# 12V_15V.net
KiCad netlist of a schematic drawn in Altium Designer
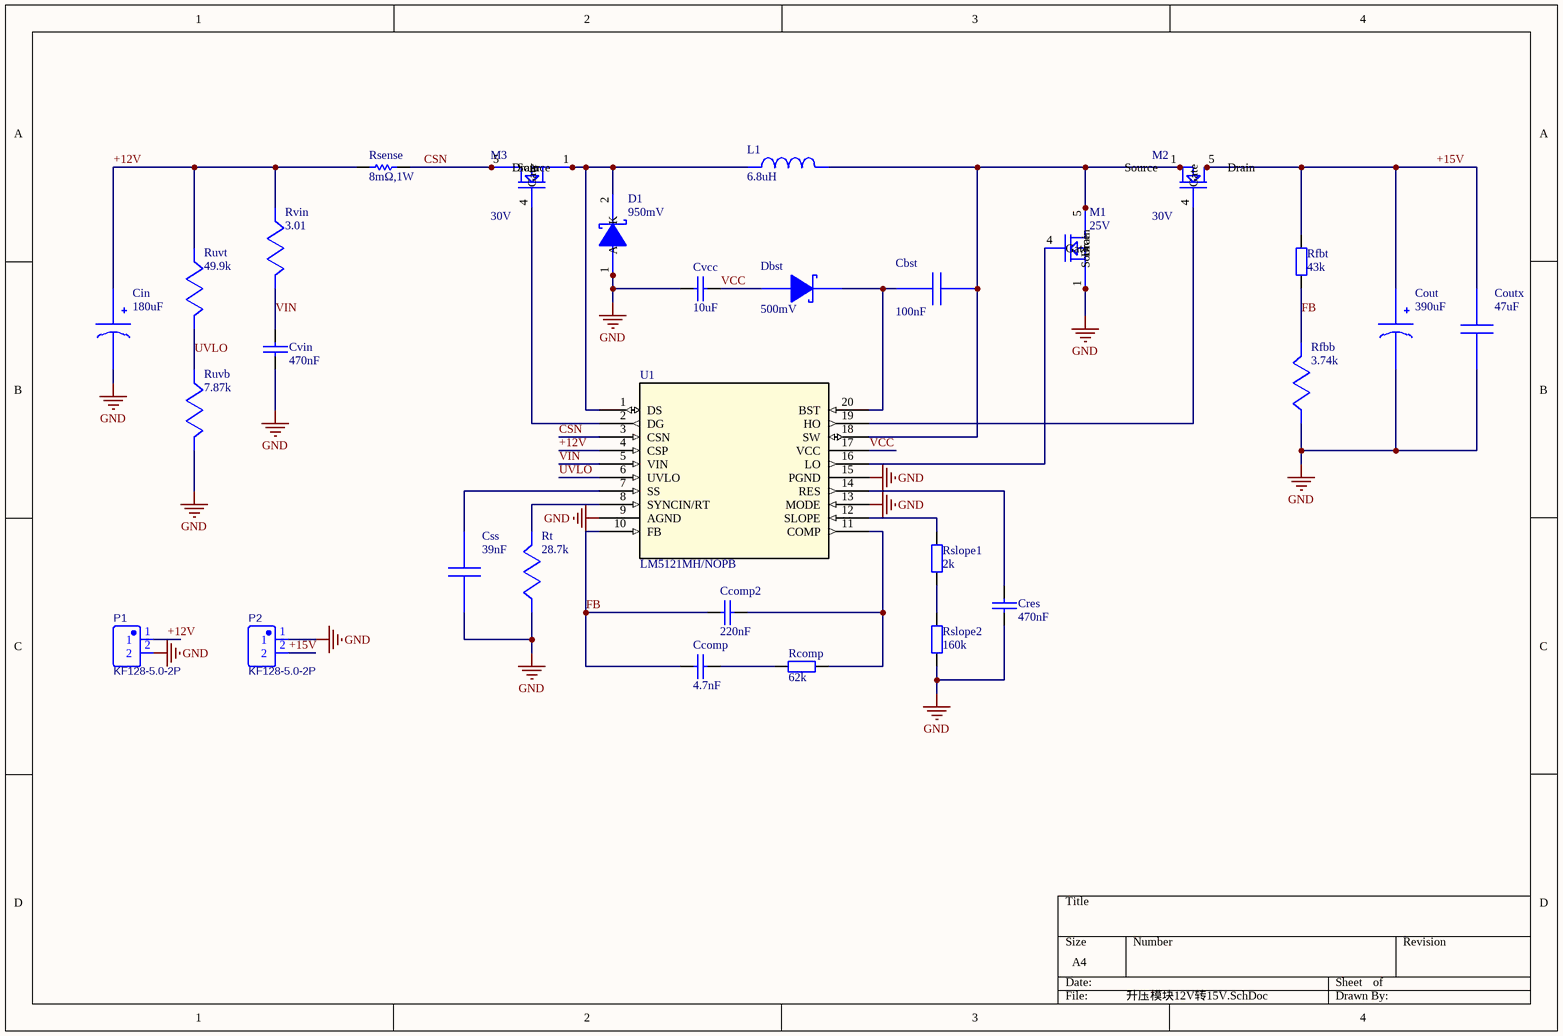
[diagram p0: 升压模块12V转15V.SchDoc]

(export (version "E")
  (design (tool "Eeschema 10.0.6"))
  (components
    (comp (ref "Cbst")
      (value "100nF")
      (footprint "0805")
      (description "C0805C104M5RACTU")
      (libsource (lib "TI") (part "Cbst"))
    )
    (comp (ref "Ccomp")
      (value "4.7nF")
      (footprint "0805C")
      (description "Capacitor")
      (libsource (lib "SCHOFDylan") (part "CAP"))
    )
    (comp (ref "Ccomp2")
      (value "220nF")
      (footprint "0805C")
      (description "Capacitor")
      (libsource (lib "SCHOFDylan") (part "CAP"))
    )
    (comp (ref "Cin")
      (value "180uF")
      (footprint "CAPSMT_62_E7")
      (description "20SVPF180M")
      (libsource (lib "TI") (part "Cin"))
    )
    (comp (ref "Cout")
      (value "390uF")
      (footprint "CAPSMT_62_E12")
      (description "20SVPF390M")
      (libsource (lib "TI") (part "Cout"))
    )
    (comp (ref "Coutx")
      (value "47uF")
      (footprint "1206")
      (description "C3216X5R1E476M16")
      (fields (field (name "MANUFACTURER PART NUMBER") "C3216X5R1E476M160AC"))
      (libsource (lib "TI") (part "Coutx"))
    )
    (comp (ref "Cres")
      (value "470nF")
      (footprint "0805C")
      (description "Capacitor")
      (libsource (lib "SCHOFDylan") (part "CAP"))
    )
    (comp (ref "Css")
      (value "39nF")
      (footprint "0402")
      (description "GRM155R71E393KA8")
      (fields (field (name "MANUFACTURER PART NUMBER") "GRM155R71E393KA88D"))
      (libsource (lib "TI") (part "Css"))
    )
    (comp (ref "Cvcc")
      (value "10uF")
      (footprint "0805C")
      (description "Capacitor")
      (libsource (lib "SCHOFDylan") (part "CAP"))
    )
    (comp (ref "Cvin")
      (value "470nF")
      (footprint "0805C")
      (description "Capacitor")
      (libsource (lib "SCHOFDylan") (part "CAP"))
    )
    (comp (ref "D1")
      (value "950mV")
      (footprint "DPAK")
      (description "SBRD10200TR")
      (libsource (lib "TI") (part "D1"))
    )
    (comp (ref "Dbst")
      (value "500mV")
      (footprint "SMB")
      (description "B220-13-F")
      (libsource (lib "TI") (part "Dbst"))
    )
    (comp (ref "L1")
      (value "6.8uH")
      (footprint "SER2915L")
      (description "SER2915L-682KL")
      (libsource (lib "SCHOFDylan") (part "电感-SER2915L"))
    )
    (comp (ref "M1")
      (value "25V")
      (footprint "DQG0008A")
      (description "CSD16327Q3")
      (libsource (lib "TI") (part "M1"))
    )
    (comp (ref "M2")
      (value "30V")
      (footprint "DQG0008A")
      (description "CSD17575Q3")
      (libsource (lib "TI") (part "M2"))
    )
    (comp (ref "M3")
      (value "30V")
      (footprint "TRANS_Fairchild_")
      (description "FDMC7660DC")
      (libsource (lib "TI") (part "M3"))
    )
    (comp (ref "P1")
      (value "KF128-5.0-2P")
      (footprint "CONN-TH_P5.00_KF128-5.0-2P")
      (fields (field (name "BOM_SUPPLIER PART") "C474950") (field (name "CONTRIBUTOR") "LCSC"))
      (libsource (lib "SCHOFDylan") (part "KF128-2P"))
    )
    (comp (ref "P2")
      (value "KF128-5.0-2P")
      (footprint "CONN-TH_P5.00_KF128-5.0-2P")
      (fields (field (name "BOM_SUPPLIER PART") "C474950") (field (name "CONTRIBUTOR") "LCSC"))
      (libsource (lib "SCHOFDylan") (part "KF128-2P"))
    )
    (comp (ref "Rcomp")
      (value "62k")
      (footprint "0805R")
      (description "Resistor")
      (libsource (lib "SCHOFDylan") (part "Res"))
    )
    (comp (ref "Rfbb")
      (value "3.74k")
      (footprint "0402")
      (description "CRCW04023K74FKED")
      (libsource (lib "TI") (part "Rfbb"))
    )
    (comp (ref "Rfbt")
      (value "43k")
      (footprint "0805R")
      (description "Resistor")
      (libsource (lib "") (part "Res_1"))
    )
    (comp (ref "Rsense") (value "8mΩ,1W") (footprint "R2512") (libsource (lib "SCHOFDylan") (part "采样电阻")))
    (comp (ref "Rslope1")
      (value "2k")
      (footprint "0805R")
      (description "Resistor")
      (libsource (lib "") (part "Res_1"))
    )
    (comp (ref "Rslope2")
      (value "160k")
      (footprint "0805R")
      (description "Resistor")
      (libsource (lib "") (part "Res_1"))
    )
    (comp (ref "Rt")
      (value "28.7k")
      (footprint "0201")
      (description "RC0201FR-0728K7L")
      (libsource (lib "TI") (part "Rt"))
    )
    (comp (ref "Ruvb")
      (value "7.87k")
      (footprint "0402")
      (description "CRCW04027K87FKED")
      (libsource (lib "TI") (part "Ruvb"))
    )
    (comp (ref "Ruvt")
      (value "49.9k")
      (footprint "0402")
      (description "CRCW040249K9FKED")
      (libsource (lib "TI") (part "Ruvt"))
    )
    (comp (ref "Rvin")
      (value "3.01")
      (footprint "0402")
      (description "CRCW04023R01FKED")
      (libsource (lib "TI") (part "Rvin"))
    )
    (comp (ref "U1")
      (value "LM5121MH/NOPB")
      (footprint "PWP20_TEX")
      (fields (field (name "COPYRIGHT") "Copyright (C) 2018 Accelerated Designs. All rights reserved"))
      (libsource (lib "SCHOFDylan") (part "LM5121MH/NOPB"))
    )
  )
  (nets
    (net (code "1") (name "/+12V") (class "Default")
      (node (ref "Cin") (pin "1") (pinfunction "+_1") (pintype "passive"))
      (node (ref "P1") (pin "1") (pinfunction "1_1") (pintype "passive"))
      (node (ref "Rsense") (pin "1") (pinfunction "1_1") (pintype "passive"))
      (node (ref "Ruvt") (pin "2") (pinfunction "2_2") (pintype "passive"))
      (node (ref "Rvin") (pin "2") (pinfunction "2_2") (pintype "passive"))
      (node (ref "U1") (pin "4") (pinfunction "CSP_4") (pintype "input"))
    )
    (net (code "2") (name "/+15V") (class "Default")
      (node (ref "Cout") (pin "1") (pinfunction "+_1") (pintype "passive"))
      (node (ref "Coutx") (pin "1") (pinfunction "1_1") (pintype "passive"))
      (node (ref "M2") (pin "5") (pinfunction "Drain_5") (pintype "passive"))
      (node (ref "M2") (pin "6") (pinfunction "Drain_6") (pintype "passive"))
      (node (ref "M2") (pin "7") (pinfunction "Drain_7") (pintype "passive"))
      (node (ref "M2") (pin "8") (pinfunction "Drain_8") (pintype "passive"))
      (node (ref "M2") (pin "9") (pinfunction "Drain_9") (pintype "passive"))
      (node (ref "P2") (pin "2") (pinfunction "2_2") (pintype "passive"))
      (node (ref "Rfbt") (pin "2") (pinfunction "2_2") (pintype "passive"))
    )
    (net (code "3") (name "/CSN") (class "Default")
      (node (ref "M3") (pin "5") (pinfunction "Drain_5") (pintype "passive"))
      (node (ref "M3") (pin "6") (pinfunction "Drain_6") (pintype "passive"))
      (node (ref "M3") (pin "7") (pinfunction "Drain_7") (pintype "passive"))
      (node (ref "M3") (pin "8") (pinfunction "Drain_8") (pintype "passive"))
      (node (ref "Rsense") (pin "2") (pinfunction "2_2") (pintype "passive"))
      (node (ref "U1") (pin "3") (pinfunction "CSN_3") (pintype "input"))
    )
    (net (code "4") (name "/FB") (class "Default")
      (node (ref "Ccomp") (pin "2") (pinfunction "2_2") (pintype "passive"))
      (node (ref "Ccomp2") (pin "2") (pinfunction "2_2") (pintype "passive"))
      (node (ref "Rfbb") (pin "1") (pinfunction "1_1") (pintype "passive"))
      (node (ref "Rfbt") (pin "1") (pinfunction "1_1") (pintype "passive"))
      (node (ref "U1") (pin "10") (pinfunction "FB_10") (pintype "input"))
    )
    (net (code "5") (name "/UVLO") (class "Default")
      (node (ref "Ruvb") (pin "2") (pinfunction "2_2") (pintype "passive"))
      (node (ref "Ruvt") (pin "1") (pinfunction "1_1") (pintype "passive"))
      (node (ref "U1") (pin "6") (pinfunction "UVLO_6") (pintype "input"))
    )
    (net (code "6") (name "/VCC") (class "Default")
      (node (ref "Cvcc") (pin "2") (pinfunction "2_2") (pintype "passive"))
      (node (ref "Dbst") (pin "2") (pinfunction "A_2") (pintype "passive"))
      (node (ref "U1") (pin "17") (pinfunction "VCC_17") (pintype "power_in"))
    )
    (net (code "7") (name "/VIN") (class "Default")
      (node (ref "Cvin") (pin "2") (pinfunction "2_2") (pintype "passive"))
      (node (ref "Rvin") (pin "1") (pinfunction "1_1") (pintype "passive"))
      (node (ref "U1") (pin "5") (pinfunction "VIN_5") (pintype "input"))
    )
    (net (code "8") (name "GND") (class "Default")
      (node (ref "Cin") (pin "2") (pinfunction "-_2") (pintype "passive"))
      (node (ref "Cout") (pin "2") (pinfunction "-_2") (pintype "passive"))
      (node (ref "Coutx") (pin "2") (pinfunction "2_2") (pintype "passive"))
      (node (ref "Cres") (pin "1") (pinfunction "1_1") (pintype "passive"))
      (node (ref "Css") (pin "2") (pinfunction "2_2") (pintype "passive"))
      (node (ref "Cvcc") (pin "1") (pinfunction "1_1") (pintype "passive"))
      (node (ref "Cvin") (pin "1") (pinfunction "1_1") (pintype "passive"))
      (node (ref "D1") (pin "1") (pinfunction "A_1") (pintype "passive"))
      (node (ref "D1") (pin "3") (pinfunction "A_3") (pintype "passive"))
      (node (ref "M1") (pin "1") (pinfunction "Source_1") (pintype "passive"))
      (node (ref "M1") (pin "2") (pinfunction "Source_2") (pintype "passive"))
      (node (ref "M1") (pin "3") (pinfunction "Source_3") (pintype "passive"))
      (node (ref "P1") (pin "2") (pinfunction "2_2") (pintype "passive"))
      (node (ref "P2") (pin "1") (pinfunction "1_1") (pintype "passive"))
      (node (ref "Rfbb") (pin "2") (pinfunction "2_2") (pintype "passive"))
      (node (ref "Rslope2") (pin "1") (pinfunction "1_1") (pintype "passive"))
      (node (ref "Rt") (pin "2") (pinfunction "2_2") (pintype "passive"))
      (node (ref "Ruvb") (pin "1") (pinfunction "1_1") (pintype "passive"))
      (node (ref "U1") (pin "13") (pinfunction "MODE_13") (pintype "input"))
      (node (ref "U1") (pin "15") (pinfunction "PGND_15") (pintype "power_in"))
      (node (ref "U1") (pin "9") (pinfunction "AGND_9") (pintype "power_in"))
    )
    (net (code "9") (name "Net-(Ccomp-Pad1)") (class "Default")
      (node (ref "Ccomp") (pin "1") (pinfunction "1_1") (pintype "passive"))
      (node (ref "Rcomp") (pin "2") (pinfunction "2_2") (pintype "passive"))
    )
    (net (code "10") (name "Net-(D1-K)") (class "Default")
      (node (ref "D1") (pin "2") (pinfunction "K_2") (pintype "passive"))
      (node (ref "L1") (pin "1") (pinfunction "1_1") (pintype "passive"))
      (node (ref "M3") (pin "1") (pinfunction "Source_1") (pintype "passive"))
      (node (ref "M3") (pin "2") (pinfunction "Source_2") (pintype "passive"))
      (node (ref "M3") (pin "3") (pinfunction "Source_3") (pintype "passive"))
      (node (ref "U1") (pin "1") (pinfunction "DS_1") (pintype "bidirectional"))
    )
    (net (code "11") (name "Net-(Dbst-K)") (class "Default")
      (node (ref "Cbst") (pin "2") (pinfunction "2_2") (pintype "passive"))
      (node (ref "Dbst") (pin "1") (pinfunction "K_1") (pintype "passive"))
      (node (ref "U1") (pin "20") (pinfunction "BST_20") (pintype "input"))
    )
    (net (code "12") (name "Net-(M1-Gate)") (class "Default")
      (node (ref "M1") (pin "4") (pinfunction "Gate_4") (pintype "passive"))
      (node (ref "U1") (pin "16") (pinfunction "LO_16") (pintype "output"))
    )
    (net (code "13") (name "Net-(M2-Gate)") (class "Default")
      (node (ref "M2") (pin "4") (pinfunction "Gate_4") (pintype "passive"))
      (node (ref "U1") (pin "19") (pinfunction "HO_19") (pintype "output"))
    )
    (net (code "14") (name "Net-(M3-Gate)") (class "Default")
      (node (ref "M3") (pin "4") (pinfunction "Gate_4") (pintype "passive"))
      (node (ref "U1") (pin "2") (pinfunction "DG_2") (pintype "output"))
    )
    (net (code "15") (name "Net-(Rslope1-Pad1)") (class "Default")
      (node (ref "Rslope1") (pin "1") (pinfunction "1_1") (pintype "passive"))
      (node (ref "Rslope2") (pin "2") (pinfunction "2_2") (pintype "passive"))
    )
    (net (code "16") (name "Net-(U1-COMP)") (class "Default")
      (node (ref "Ccomp2") (pin "1") (pinfunction "1_1") (pintype "passive"))
      (node (ref "Rcomp") (pin "1") (pinfunction "1_1") (pintype "passive"))
      (node (ref "U1") (pin "11") (pinfunction "COMP_11") (pintype "output"))
    )
    (net (code "17") (name "Net-(U1-RES)") (class "Default")
      (node (ref "Cres") (pin "2") (pinfunction "2_2") (pintype "passive"))
      (node (ref "U1") (pin "14") (pinfunction "RES_14") (pintype "output"))
    )
    (net (code "18") (name "Net-(U1-SLOPE)") (class "Default")
      (node (ref "Rslope1") (pin "2") (pinfunction "2_2") (pintype "passive"))
      (node (ref "U1") (pin "12") (pinfunction "SLOPE_12") (pintype "input"))
    )
    (net (code "19") (name "Net-(U1-SS)") (class "Default")
      (node (ref "Css") (pin "1") (pinfunction "1_1") (pintype "passive"))
      (node (ref "U1") (pin "7") (pinfunction "SS_7") (pintype "input"))
    )
    (net (code "20") (name "Net-(U1-SW)") (class "Default")
      (node (ref "Cbst") (pin "1") (pinfunction "1_1") (pintype "passive"))
      (node (ref "L1") (pin "2") (pinfunction "2_2") (pintype "passive"))
      (node (ref "M1") (pin "5") (pinfunction "Drain_5") (pintype "passive"))
      (node (ref "M1") (pin "6") (pinfunction "Drain_6") (pintype "passive"))
      (node (ref "M1") (pin "7") (pinfunction "Drain_7") (pintype "passive"))
      (node (ref "M1") (pin "8") (pinfunction "Drain_8") (pintype "passive"))
      (node (ref "M1") (pin "9") (pinfunction "Drain_9") (pintype "passive"))
      (node (ref "M2") (pin "1") (pinfunction "Source_1") (pintype "passive"))
      (node (ref "M2") (pin "2") (pinfunction "Source_2") (pintype "passive"))
      (node (ref "M2") (pin "3") (pinfunction "Source_3") (pintype "passive"))
      (node (ref "U1") (pin "18") (pinfunction "SW_18") (pintype "bidirectional"))
    )
    (net (code "21") (name "Net-(U1-SYNCIN{slash}RT)") (class "Default")
      (node (ref "Rt") (pin "1") (pinfunction "1_1") (pintype "passive"))
      (node (ref "U1") (pin "8") (pinfunction "SYNCIN/RT_8") (pintype "input"))
    )
  )
)
